# Sheet1.net
KiCad netlist of a schematic drawn in Altium Designer
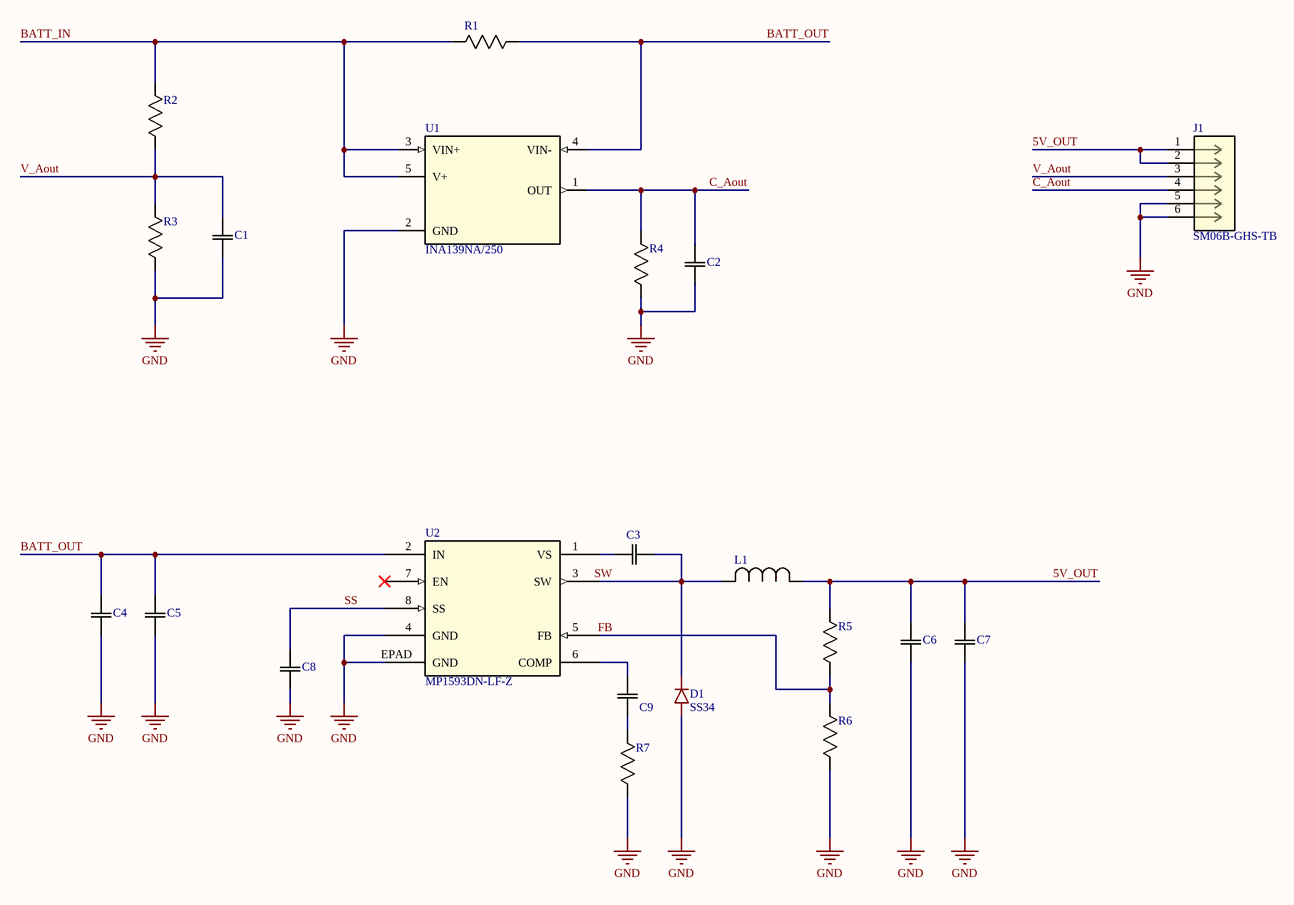
[diagram p0: Sheet1.SchDoc]

(export (version "E")
  (design (tool "Eeschema 10.0.6"))
  (components
    (comp (ref "C1")
      (value "CC0402KRX7R9BB104")
      (footprint "CAP_0402")
      (description "50V 100nF X7R ±10% 0402 Multilayer Ceramic Capacitors MLCC - SMD/SMT ROHS")
      (fields (field (name "MANUFACTURER") "Yageo Group") (field (name "TOLERANCE") "10%"))
      (libsource (lib "Schlib1") (part "CC0402KRX7R9BB104"))
    )
    (comp (ref "C2")
      (value "CC0402KRX7R9BB104")
      (footprint "CAP_0402")
      (description "50V 100nF X7R ±10% 0402 Multilayer Ceramic Capacitors MLCC - SMD/SMT ROHS")
      (fields (field (name "MANUFACTURER") "Yageo Group") (field (name "TOLERANCE") "10%"))
      (libsource (lib "Schlib1") (part "CC0402KRX7R9BB104"))
    )
    (comp (ref "C3")
      (value "C0402C103K5RACTU")
      (footprint "CAP_0402")
      (description "Multilayer Ceramic Capacitors MLCC - SMD/SMT 50V 0.01uF X7R 0402 10%")
      (fields (field (name "MANUFACTURER") "KEMET") (field (name "TOLERANCE") "10%"))
      (libsource (lib "Schlib1") (part "C0402C103K5RACTU"))
    )
    (comp (ref "C4")
      (value "CC1210KKX7R9BB106")
      (footprint "CAP_1210")
      (description "50V 10uF X7R ±10% 1210 Multilayer Ceramic Capacitors MLCC - SMD/SMT ROHS")
      (fields (field (name "MANUFACTURER") "Yageo Group") (field (name "TOLERANCE") "10%"))
      (libsource (lib "Schlib1") (part "CC1210KKX7R9BB106"))
    )
    (comp (ref "C5")
      (value "CC1210KKX7R9BB106")
      (footprint "CAP_1210")
      (description "50V 10uF X7R ±10% 1210 Multilayer Ceramic Capacitors MLCC - SMD/SMT ROHS")
      (fields (field (name "MANUFACTURER") "Yageo Group") (field (name "TOLERANCE") "10%"))
      (libsource (lib "Schlib1") (part "CC1210KKX7R9BB106"))
    )
    (comp (ref "C6")
      (value "GRM32ER71E226ME15L")
      (footprint "CAP_1210")
      (description "22 µF ±20% 25V Ceramic Capacitor X7R 1210 (3225 Metric)")
      (fields (field (name "COPYRIGHT") "Copyright (C) 2025 Ultra Librarian. All rights reserved."))
      (libsource (lib "Schlib1") (part "GRM32ER71E226ME15L"))
    )
    (comp (ref "C7")
      (value "GRM32ER71E226ME15L")
      (footprint "CAP_1210")
      (description "22 µF ±20% 25V Ceramic Capacitor X7R 1210 (3225 Metric)")
      (fields (field (name "COPYRIGHT") "Copyright (C) 2025 Ultra Librarian. All rights reserved."))
      (libsource (lib "Schlib1") (part "GRM32ER71E226ME15L"))
    )
    (comp (ref "C8")
      (value "CC0402KRX7R9BB104")
      (footprint "CAP_0402")
      (description "50V 100nF X7R ±10% 0402 Multilayer Ceramic Capacitors MLCC - SMD/SMT ROHS")
      (fields (field (name "MANUFACTURER") "Yageo Group") (field (name "TOLERANCE") "10%"))
      (libsource (lib "Schlib1") (part "CC0402KRX7R9BB104"))
    )
    (comp (ref "C9")
      (value "C0402C103K5RACTU")
      (footprint "CAP_0402")
      (description "Multilayer Ceramic Capacitors MLCC - SMD/SMT 50V 0.01uF X7R 0402 10%")
      (fields (field (name "MANUFACTURER") "KEMET") (field (name "TOLERANCE") "10%"))
      (libsource (lib "Schlib1") (part "C0402C103K5RACTU"))
    )
    (comp (ref "D1")
      (value "SS34")
      (footprint "SMB_ONS")
      (description "Diode 40 V 3A Surface Mount DO-214AB (SMC)")
      (fields (field (name "COPYRIGHT") "Copyright (C) 2025 Ultra Librarian. All rights reserved."))
      (libsource (lib "Schlib1") (part "SS34"))
    )
    (comp (ref "J1")
      (value "SM06B-GHS-TB")
      (footprint "CONN_SM06B-GHS-TB_JST")
      (description "Connector Header Surface Mount, Right Angle 6 position 0.049\" (1.25mm)")
      (fields (field (name "COPYRIGHT") "Copyright (C) 2025 Ultra Librarian. All rights reserved."))
      (libsource (lib "Schlib1") (part "SM06B-GHS-TB"))
    )
    (comp (ref "L1")
      (value "SRR1260-150M")
      (footprint "IND_BOURNS_SRR1260")
      (description "15 µH Shielded Drum Core, Wirewound Inductor 5 A 27mOhm Max Nonstandard")
      (fields (field (name "COPYRIGHT") "Copyright (C) 2025 Ultra Librarian. All rights reserved."))
      (libsource (lib "Schlib1") (part "SRR1260-150M"))
    )
    (comp (ref "R1")
      (value "PA2512FKE7T0U5E")
      (footprint "RES_PA2512_YAG-L")
      (fields (field (name "COPYRIGHT") "Copyright (C) 2025 Ultra Librarian. All rights reserved."))
      (libsource (lib "Schlib1") (part "PA2512FKE7T0U5E"))
    )
    (comp (ref "R2")
      (value "ERJ-2RKF1372X")
      (footprint "RES_0402")
      (description "Res Thick Film 0402 13.7K Ohm 1% 0.1W ±100ppm/°C Molded SMD Punched Carrier T/R")
      (fields (field (name "MANUFACTURER") "Panasonic") (field (name "TOLERANCE") "1%"))
      (libsource (lib "Schlib1") (part "ERJ-2RKF1372X"))
    )
    (comp (ref "R3")
      (value "ERJ-2GEJ152X")
      (footprint "RES_0402")
      (description "Res Thick Film 0402 1.5K Ohm 5% 0.1W(1/10W) +/-200ppm/ßC SMD Automotive T/R")
      (fields (field (name "MANUFACTURER") "Panasonic") (field (name "TOLERANCE") "5%"))
      (libsource (lib "Schlib1") (part "ERJ-2GEJ152X"))
    )
    (comp (ref "R4")
      (value "ERJ-2GEJ104X")
      (footprint "RES_0402")
      (description "Res Thick Film 0402 100K Ohm 5% 0.1W(1/10W) +/-200ppm/ßC SMD Automotive T/R")
      (fields (field (name "MANUFACTURER") "Panasonic") (field (name "TOLERANCE") "5%"))
      (libsource (lib "Schlib1") (part "ERJ-2GEJ104X"))
    )
    (comp (ref "R5")
      (value "CRGP0402F33K")
      (footprint "RES_0402")
      (description "Res Thick Film 0402 33K Ohm 1% 0.125W(1/8W) ±100ppm/C Pad SMD T/R Automotive AEC-Q200")
      (fields (field (name "MANUFACTURER") "TE Connectivity") (field (name "TOLERANCE") "1%"))
      (libsource (lib "Schlib1") (part "CRGP0402F33K"))
    )
    (comp (ref "R6")
      (value "CRGP0402F10K")
      (footprint "RES_0402")
      (description "Res Thick Film 0402 10K Ohm 1% 0.125W(1/8W) ±100ppm/C Pad SMD T/R Automotive AEC-Q200")
      (fields (field (name "MANUFACTURER") "TE Connectivity") (field (name "TOLERANCE") "1%"))
      (libsource (lib "Schlib1") (part "CRGP0402F10K"))
    )
    (comp (ref "R7")
      (value "RK73H1ETTP7501F")
      (footprint "RES_0402")
      (description "Res Thick Film 0402 7.5K Ohm 1% 0.1W(1/10W) ±100ppm/C Pad SMD Automotive T/R")
      (fields (field (name "MANUFACTURER") "KOA Speer") (field (name "TOLERANCE") "1%"))
      (libsource (lib "Schlib1") (part "RK73H1ETTP7501F"))
    )
    (comp (ref "U1")
      (value "INA139NA/250")
      (footprint "DBV0005A_N")
      (description "2.7 to 36V, 440kHz Variable gain current sense amplifier 5-SOT-23 -40 to 125")
      (fields (field (name "COPYRIGHT") "Copyright (C) 2025 Ultra Librarian. All rights reserved."))
      (libsource (lib "Schlib1") (part "INA139NA250"))
    )
    (comp (ref "U2")
      (value "MP1593DN-LF-Z")
      (footprint "SOIC8E_MNP")
      (description "3A 28V 385KHz Step-Down Converter")
      (fields (field (name "COPYRIGHT") "Copyright (C) 2025 Ultra Librarian. All rights reserved."))
      (libsource (lib "Schlib1") (part "MP1593DN-LF-Z"))
    )
  )
  (nets
    (net (code "1") (name "/5V_OUT") (class "Default")
      (node (ref "C6") (pin "2") (pinfunction "2_2") (pintype "passive"))
      (node (ref "C7") (pin "2") (pinfunction "2_2") (pintype "passive"))
      (node (ref "J1") (pin "1") (pinfunction "1_1") (pintype "passive"))
      (node (ref "J1") (pin "2") (pinfunction "2_2") (pintype "passive"))
      (node (ref "L1") (pin "1") (pinfunction "1_1") (pintype "passive"))
      (node (ref "R5") (pin "1") (pinfunction "1_1") (pintype "passive"))
    )
    (net (code "2") (name "/BATT_IN") (class "Default")
      (node (ref "R1") (pin "1") (pinfunction "1_1") (pintype "passive"))
      (node (ref "R2") (pin "1") (pinfunction "1_1") (pintype "passive"))
      (node (ref "U1") (pin "3") (pinfunction "VIN+_3") (pintype "input"))
      (node (ref "U1") (pin "5") (pinfunction "V+_5") (pintype "power_in"))
    )
    (net (code "3") (name "/BATT_OUT") (class "Default")
      (node (ref "C4") (pin "1") (pinfunction "1_1") (pintype "passive"))
      (node (ref "C5") (pin "2") (pinfunction "2_2") (pintype "passive"))
      (node (ref "R1") (pin "2") (pinfunction "2_2") (pintype "passive"))
      (node (ref "U1") (pin "4") (pinfunction "VIN-_4") (pintype "input"))
      (node (ref "U2") (pin "2") (pinfunction "IN_2") (pintype "power_in"))
    )
    (net (code "4") (name "/C_Aout") (class "Default")
      (node (ref "C2") (pin "2") (pinfunction "2_2") (pintype "passive"))
      (node (ref "J1") (pin "4") (pinfunction "4_4") (pintype "passive"))
      (node (ref "R4") (pin "1") (pinfunction "1_1") (pintype "passive"))
      (node (ref "U1") (pin "1") (pinfunction "OUT_1") (pintype "output"))
    )
    (net (code "5") (name "/FB") (class "Default")
      (node (ref "R5") (pin "2") (pinfunction "2_2") (pintype "passive"))
      (node (ref "R6") (pin "1") (pinfunction "1_1") (pintype "passive"))
      (node (ref "U2") (pin "5") (pinfunction "FB_5") (pintype "input"))
    )
    (net (code "6") (name "/SS") (class "Default")
      (node (ref "C8") (pin "2") (pinfunction "2_2") (pintype "passive"))
      (node (ref "U2") (pin "8") (pinfunction "SS_8") (pintype "input"))
    )
    (net (code "7") (name "/SW") (class "Default")
      (node (ref "C3") (pin "2") (pinfunction "2_2") (pintype "passive"))
      (node (ref "D1") (pin "1") (pinfunction "K_1") (pintype "passive"))
      (node (ref "L1") (pin "2") (pinfunction "2_2") (pintype "passive"))
      (node (ref "U2") (pin "3") (pinfunction "SW_3") (pintype "output"))
    )
    (net (code "8") (name "/V_Aout") (class "Default")
      (node (ref "C1") (pin "2") (pinfunction "2_2") (pintype "passive"))
      (node (ref "J1") (pin "3") (pinfunction "3_3") (pintype "passive"))
      (node (ref "R2") (pin "2") (pinfunction "2_2") (pintype "passive"))
      (node (ref "R3") (pin "1") (pinfunction "1_1") (pintype "passive"))
    )
    (net (code "9") (name "GND") (class "Default")
      (node (ref "C1") (pin "1") (pinfunction "1_1") (pintype "passive"))
      (node (ref "C2") (pin "1") (pinfunction "1_1") (pintype "passive"))
      (node (ref "C4") (pin "2") (pinfunction "2_2") (pintype "passive"))
      (node (ref "C5") (pin "1") (pinfunction "1_1") (pintype "passive"))
      (node (ref "C6") (pin "1") (pinfunction "1_1") (pintype "passive"))
      (node (ref "C7") (pin "1") (pinfunction "1_1") (pintype "passive"))
      (node (ref "C8") (pin "1") (pinfunction "1_1") (pintype "passive"))
      (node (ref "D1") (pin "2") (pinfunction "A_2") (pintype "passive"))
      (node (ref "J1") (pin "5") (pinfunction "5_5") (pintype "passive"))
      (node (ref "J1") (pin "6") (pinfunction "6_6") (pintype "passive"))
      (node (ref "R3") (pin "2") (pinfunction "2_2") (pintype "passive"))
      (node (ref "R4") (pin "2") (pinfunction "2_2") (pintype "passive"))
      (node (ref "R6") (pin "2") (pinfunction "2_2") (pintype "passive"))
      (node (ref "R7") (pin "1") (pinfunction "1_1") (pintype "passive"))
      (node (ref "U1") (pin "2") (pinfunction "GND_2") (pintype "power_in"))
      (node (ref "U2") (pin "4") (pinfunction "GND_4") (pintype "power_in"))
      (node (ref "U2") (pin "EPAD") (pinfunction "GND_EPAD") (pintype "power_in"))
    )
    (net (code "10") (name "Net-(C9-Pad1)") (class "Default")
      (node (ref "C9") (pin "1") (pinfunction "1_1") (pintype "passive"))
      (node (ref "R7") (pin "2") (pinfunction "2_2") (pintype "passive"))
    )
    (net (code "11") (name "Net-(U2-COMP)") (class "Default")
      (node (ref "C9") (pin "2") (pinfunction "2_2") (pintype "passive"))
      (node (ref "U2") (pin "6") (pinfunction "COMP_6") (pintype "passive"))
    )
    (net (code "12") (name "Net-(U2-VS)") (class "Default")
      (node (ref "C3") (pin "1") (pinfunction "1_1") (pintype "passive"))
      (node (ref "U2") (pin "1") (pinfunction "VS_1") (pintype "power_in"))
    )
    (net (code "13") (name "unconnected-(U2-EN-Pad7)") (class "Default")
      (node (ref "U2") (pin "7") (pinfunction "EN_7") (pintype "input+no_connect"))
    )
  )
)
